# BasicGates.net
KiCad netlist of a schematic drawn in EAGLE
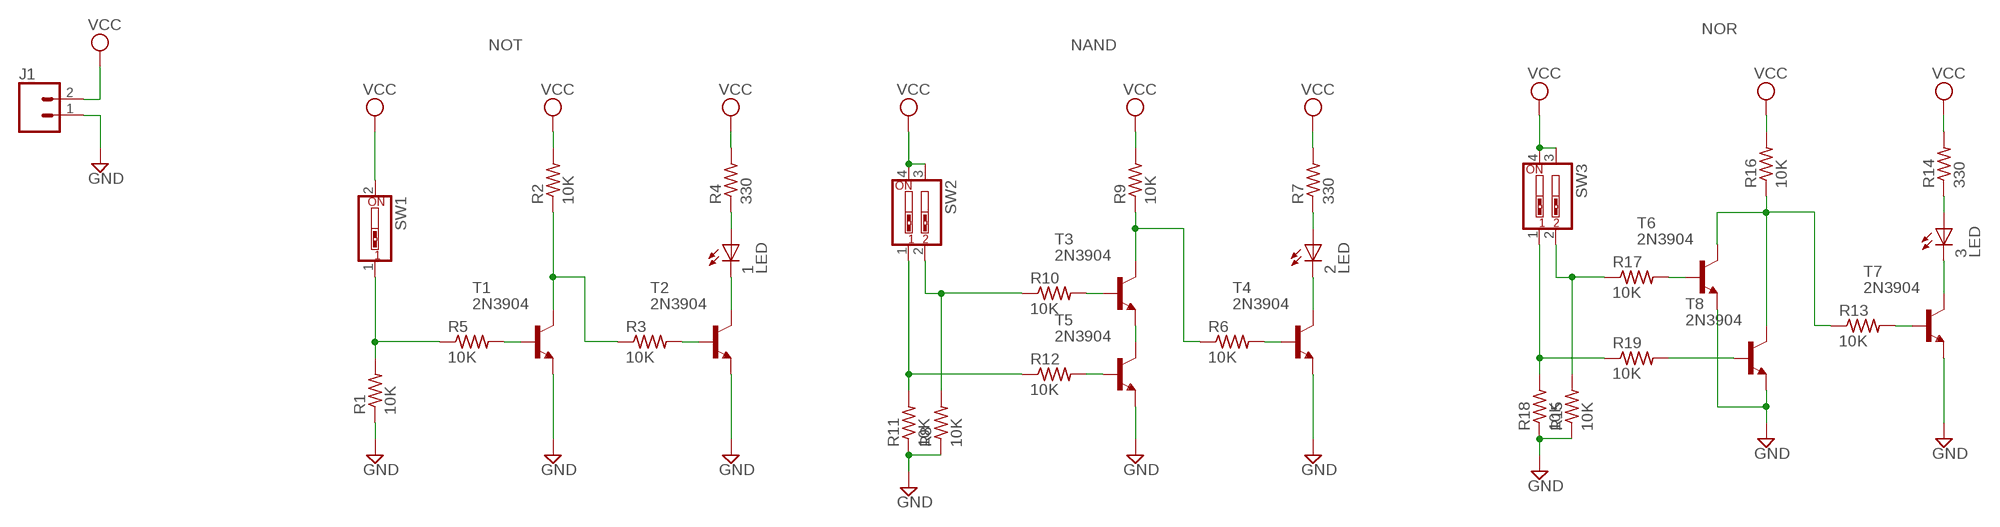
[diagram p0: schematic, sheet 1]

(export (version "E")
  (design (tool "Eeschema 10.0.6"))
  (components
    (comp (ref "1")
      (value "LED")
      (footprint "eagle-import:LED5MM")
      (libsource (lib "eagle-import") (part "LED5MM"))
    )
    (comp (ref "2")
      (value "LED")
      (footprint "eagle-import:LED5MM")
      (libsource (lib "eagle-import") (part "LED5MM"))
    )
    (comp (ref "3")
      (value "LED")
      (footprint "eagle-import:LED5MM")
      (libsource (lib "eagle-import") (part "LED5MM"))
    )
    (comp (ref "J1")
      (value "CONN_02")
      (footprint "eagle-import:1X02")
      (libsource (lib "eagle-import") (part "CONN_02"))
    )
    (comp (ref "R1")
      (value "10K")
      (footprint "eagle-import:0309_10")
      (libsource (lib "eagle-import") (part "R-US_0309/10"))
    )
    (comp (ref "R2")
      (value "10K")
      (footprint "eagle-import:0309_10")
      (libsource (lib "eagle-import") (part "R-US_0309/10"))
    )
    (comp (ref "R3")
      (value "10K")
      (footprint "eagle-import:0309_10")
      (libsource (lib "eagle-import") (part "R-US_0309/10"))
    )
    (comp (ref "R4")
      (value "330")
      (footprint "eagle-import:0309_10")
      (libsource (lib "eagle-import") (part "R-US_0309/10"))
    )
    (comp (ref "R5")
      (value "10K")
      (footprint "eagle-import:0309_10")
      (libsource (lib "eagle-import") (part "R-US_0309/10"))
    )
    (comp (ref "R6")
      (value "10K")
      (footprint "eagle-import:0309_10")
      (libsource (lib "eagle-import") (part "R-US_0309/10"))
    )
    (comp (ref "R7")
      (value "330")
      (footprint "eagle-import:0309_10")
      (libsource (lib "eagle-import") (part "R-US_0309/10"))
    )
    (comp (ref "R8")
      (value "10K")
      (footprint "eagle-import:0309_10")
      (libsource (lib "eagle-import") (part "R-US_0309/10"))
    )
    (comp (ref "R9")
      (value "10K")
      (footprint "eagle-import:0309_10")
      (libsource (lib "eagle-import") (part "R-US_0309/10"))
    )
    (comp (ref "R10")
      (value "10K")
      (footprint "eagle-import:0309_10")
      (libsource (lib "eagle-import") (part "R-US_0309/10"))
    )
    (comp (ref "R11")
      (value "10K")
      (footprint "eagle-import:0309_10")
      (libsource (lib "eagle-import") (part "R-US_0309/10"))
    )
    (comp (ref "R12")
      (value "10K")
      (footprint "eagle-import:0309_10")
      (libsource (lib "eagle-import") (part "R-US_0309/10"))
    )
    (comp (ref "R13")
      (value "10K")
      (footprint "eagle-import:0309_10")
      (libsource (lib "eagle-import") (part "R-US_0309/10"))
    )
    (comp (ref "R14")
      (value "330")
      (footprint "eagle-import:0309_10")
      (libsource (lib "eagle-import") (part "R-US_0309/10"))
    )
    (comp (ref "R15")
      (value "10K")
      (footprint "eagle-import:0309_10")
      (libsource (lib "eagle-import") (part "R-US_0309/10"))
    )
    (comp (ref "R16")
      (value "10K")
      (footprint "eagle-import:0309_10")
      (libsource (lib "eagle-import") (part "R-US_0309/10"))
    )
    (comp (ref "R17")
      (value "10K")
      (footprint "eagle-import:0309_10")
      (libsource (lib "eagle-import") (part "R-US_0309/10"))
    )
    (comp (ref "R18")
      (value "10K")
      (footprint "eagle-import:0309_10")
      (libsource (lib "eagle-import") (part "R-US_0309/10"))
    )
    (comp (ref "R19")
      (value "10K")
      (footprint "eagle-import:0309_10")
      (libsource (lib "eagle-import") (part "R-US_0309/10"))
    )
    (comp (ref "SW1")
      (value "SW_DIP-1")
      (footprint "eagle-import:EDG-01")
      (libsource (lib "eagle-import") (part "SW_DIP-1"))
    )
    (comp (ref "SW2")
      (value "SW_DIP-2")
      (footprint "eagle-import:EDG-02")
      (libsource (lib "eagle-import") (part "SW_DIP-2"))
    )
    (comp (ref "SW3")
      (value "SW_DIP-2")
      (footprint "eagle-import:EDG-02")
      (libsource (lib "eagle-import") (part "SW_DIP-2"))
    )
    (comp (ref "T1")
      (value "2N3904")
      (footprint "eagle-import:TO92")
      (libsource (lib "eagle-import") (part "2N3904"))
    )
    (comp (ref "T2")
      (value "2N3904")
      (footprint "eagle-import:TO92")
      (libsource (lib "eagle-import") (part "2N3904"))
    )
    (comp (ref "T3")
      (value "2N3904")
      (footprint "eagle-import:TO92")
      (libsource (lib "eagle-import") (part "2N3904"))
    )
    (comp (ref "T4")
      (value "2N3904")
      (footprint "eagle-import:TO92")
      (libsource (lib "eagle-import") (part "2N3904"))
    )
    (comp (ref "T5")
      (value "2N3904")
      (footprint "eagle-import:TO92")
      (libsource (lib "eagle-import") (part "2N3904"))
    )
    (comp (ref "T6")
      (value "2N3904")
      (footprint "eagle-import:TO92")
      (libsource (lib "eagle-import") (part "2N3904"))
    )
    (comp (ref "T7")
      (value "2N3904")
      (footprint "eagle-import:TO92")
      (libsource (lib "eagle-import") (part "2N3904"))
    )
    (comp (ref "T8")
      (value "2N3904")
      (footprint "eagle-import:TO92")
      (libsource (lib "eagle-import") (part "2N3904"))
    )
  )
  (nets
    (net (code "1") (name "GND") (class "Default")
      (node (ref "J1") (pin "1") (pinfunction "1_1") (pintype "passive"))
      (node (ref "R1") (pin "1") (pinfunction "1_1") (pintype "passive"))
      (node (ref "R11") (pin "1") (pinfunction "1_1") (pintype "passive"))
      (node (ref "R15") (pin "1") (pinfunction "1_1") (pintype "passive"))
      (node (ref "R18") (pin "1") (pinfunction "1_1") (pintype "passive"))
      (node (ref "R8") (pin "1") (pinfunction "1_1") (pintype "passive"))
      (node (ref "T1") (pin "3") (pinfunction "E_3") (pintype "passive"))
      (node (ref "T2") (pin "3") (pinfunction "E_3") (pintype "passive"))
      (node (ref "T4") (pin "3") (pinfunction "E_3") (pintype "passive"))
      (node (ref "T5") (pin "3") (pinfunction "E_3") (pintype "passive"))
      (node (ref "T6") (pin "3") (pinfunction "E_3") (pintype "passive"))
      (node (ref "T7") (pin "3") (pinfunction "E_3") (pintype "passive"))
      (node (ref "T8") (pin "3") (pinfunction "E_3") (pintype "passive"))
    )
    (net (code "2") (name "Net-(1-C)") (class "Default")
      (node (ref "1") (pin "K") (pinfunction "C_K") (pintype "passive"))
      (node (ref "T2") (pin "1") (pinfunction "C_1") (pintype "passive"))
    )
    (net (code "3") (name "Net-(1-PadA)") (class "Default")
      (node (ref "1") (pin "A") (pinfunction "A_A") (pintype "passive"))
      (node (ref "R4") (pin "1") (pinfunction "1_1") (pintype "passive"))
    )
    (net (code "4") (name "Net-(2-C)") (class "Default")
      (node (ref "2") (pin "K") (pinfunction "C_K") (pintype "passive"))
      (node (ref "T4") (pin "1") (pinfunction "C_1") (pintype "passive"))
    )
    (net (code "5") (name "Net-(2-PadA)") (class "Default")
      (node (ref "2") (pin "A") (pinfunction "A_A") (pintype "passive"))
      (node (ref "R7") (pin "1") (pinfunction "1_1") (pintype "passive"))
    )
    (net (code "6") (name "Net-(3-C)") (class "Default")
      (node (ref "3") (pin "K") (pinfunction "C_K") (pintype "passive"))
      (node (ref "T7") (pin "1") (pinfunction "C_1") (pintype "passive"))
    )
    (net (code "7") (name "Net-(3-PadA)") (class "Default")
      (node (ref "3") (pin "A") (pinfunction "A_A") (pintype "passive"))
      (node (ref "R14") (pin "1") (pinfunction "1_1") (pintype "passive"))
    )
    (net (code "8") (name "Net-(R1-Pad2)") (class "Default")
      (node (ref "R1") (pin "2") (pinfunction "2_2") (pintype "passive"))
      (node (ref "R5") (pin "1") (pinfunction "1_1") (pintype "passive"))
      (node (ref "SW1") (pin "1") (pinfunction "1_1") (pintype "passive"))
    )
    (net (code "9") (name "Net-(R10-Pad1)") (class "Default")
      (node (ref "R10") (pin "1") (pinfunction "1_1") (pintype "passive"))
      (node (ref "R8") (pin "2") (pinfunction "2_2") (pintype "passive"))
      (node (ref "SW2") (pin "2") (pinfunction "2_2") (pintype "passive"))
    )
    (net (code "10") (name "Net-(R11-Pad2)") (class "Default")
      (node (ref "R11") (pin "2") (pinfunction "2_2") (pintype "passive"))
      (node (ref "R12") (pin "1") (pinfunction "1_1") (pintype "passive"))
      (node (ref "SW2") (pin "1") (pinfunction "1_1") (pintype "passive"))
    )
    (net (code "11") (name "Net-(R15-Pad2)") (class "Default")
      (node (ref "R15") (pin "2") (pinfunction "2_2") (pintype "passive"))
      (node (ref "R17") (pin "1") (pinfunction "1_1") (pintype "passive"))
      (node (ref "SW3") (pin "2") (pinfunction "2_2") (pintype "passive"))
    )
    (net (code "12") (name "Net-(R18-Pad2)") (class "Default")
      (node (ref "R18") (pin "2") (pinfunction "2_2") (pintype "passive"))
      (node (ref "R19") (pin "1") (pinfunction "1_1") (pintype "passive"))
      (node (ref "SW3") (pin "1") (pinfunction "1_1") (pintype "passive"))
    )
    (net (code "13") (name "Net-(T1-B)") (class "Default")
      (node (ref "R5") (pin "2") (pinfunction "2_2") (pintype "passive"))
      (node (ref "T1") (pin "2") (pinfunction "B_2") (pintype "passive"))
    )
    (net (code "14") (name "Net-(T1-C)") (class "Default")
      (node (ref "R2") (pin "1") (pinfunction "1_1") (pintype "passive"))
      (node (ref "R3") (pin "1") (pinfunction "1_1") (pintype "passive"))
      (node (ref "T1") (pin "1") (pinfunction "C_1") (pintype "passive"))
    )
    (net (code "15") (name "Net-(T2-B)") (class "Default")
      (node (ref "R3") (pin "2") (pinfunction "2_2") (pintype "passive"))
      (node (ref "T2") (pin "2") (pinfunction "B_2") (pintype "passive"))
    )
    (net (code "16") (name "Net-(T3-B)") (class "Default")
      (node (ref "R10") (pin "2") (pinfunction "2_2") (pintype "passive"))
      (node (ref "T3") (pin "2") (pinfunction "B_2") (pintype "passive"))
    )
    (net (code "17") (name "Net-(T3-C)") (class "Default")
      (node (ref "R6") (pin "1") (pinfunction "1_1") (pintype "passive"))
      (node (ref "R9") (pin "1") (pinfunction "1_1") (pintype "passive"))
      (node (ref "T3") (pin "1") (pinfunction "C_1") (pintype "passive"))
    )
    (net (code "18") (name "Net-(T3-E)") (class "Default")
      (node (ref "T3") (pin "3") (pinfunction "E_3") (pintype "passive"))
      (node (ref "T5") (pin "1") (pinfunction "C_1") (pintype "passive"))
    )
    (net (code "19") (name "Net-(T4-B)") (class "Default")
      (node (ref "R6") (pin "2") (pinfunction "2_2") (pintype "passive"))
      (node (ref "T4") (pin "2") (pinfunction "B_2") (pintype "passive"))
    )
    (net (code "20") (name "Net-(T5-B)") (class "Default")
      (node (ref "R12") (pin "2") (pinfunction "2_2") (pintype "passive"))
      (node (ref "T5") (pin "2") (pinfunction "B_2") (pintype "passive"))
    )
    (net (code "21") (name "Net-(T6-B)") (class "Default")
      (node (ref "R17") (pin "2") (pinfunction "2_2") (pintype "passive"))
      (node (ref "T6") (pin "2") (pinfunction "B_2") (pintype "passive"))
    )
    (net (code "22") (name "Net-(T6-C)") (class "Default")
      (node (ref "R13") (pin "1") (pinfunction "1_1") (pintype "passive"))
      (node (ref "R16") (pin "1") (pinfunction "1_1") (pintype "passive"))
      (node (ref "T6") (pin "1") (pinfunction "C_1") (pintype "passive"))
      (node (ref "T8") (pin "1") (pinfunction "C_1") (pintype "passive"))
    )
    (net (code "23") (name "Net-(T7-B)") (class "Default")
      (node (ref "R13") (pin "2") (pinfunction "2_2") (pintype "passive"))
      (node (ref "T7") (pin "2") (pinfunction "B_2") (pintype "passive"))
    )
    (net (code "24") (name "Net-(T8-B)") (class "Default")
      (node (ref "R19") (pin "2") (pinfunction "2_2") (pintype "passive"))
      (node (ref "T8") (pin "2") (pinfunction "B_2") (pintype "passive"))
    )
    (net (code "25") (name "VCC") (class "Default")
      (node (ref "J1") (pin "2") (pinfunction "2_2") (pintype "passive"))
      (node (ref "R14") (pin "2") (pinfunction "2_2") (pintype "passive"))
      (node (ref "R16") (pin "2") (pinfunction "2_2") (pintype "passive"))
      (node (ref "R2") (pin "2") (pinfunction "2_2") (pintype "passive"))
      (node (ref "R4") (pin "2") (pinfunction "2_2") (pintype "passive"))
      (node (ref "R7") (pin "2") (pinfunction "2_2") (pintype "passive"))
      (node (ref "R9") (pin "2") (pinfunction "2_2") (pintype "passive"))
      (node (ref "SW1") (pin "2") (pinfunction "2_2") (pintype "passive"))
      (node (ref "SW2") (pin "3") (pinfunction "3_3") (pintype "passive"))
      (node (ref "SW2") (pin "4") (pinfunction "4_4") (pintype "passive"))
      (node (ref "SW3") (pin "3") (pinfunction "3_3") (pintype "passive"))
      (node (ref "SW3") (pin "4") (pinfunction "4_4") (pintype "passive"))
    )
  )
)
